# BMS_Rev2_SSR.net
KiCad netlist of a schematic drawn in EAGLE
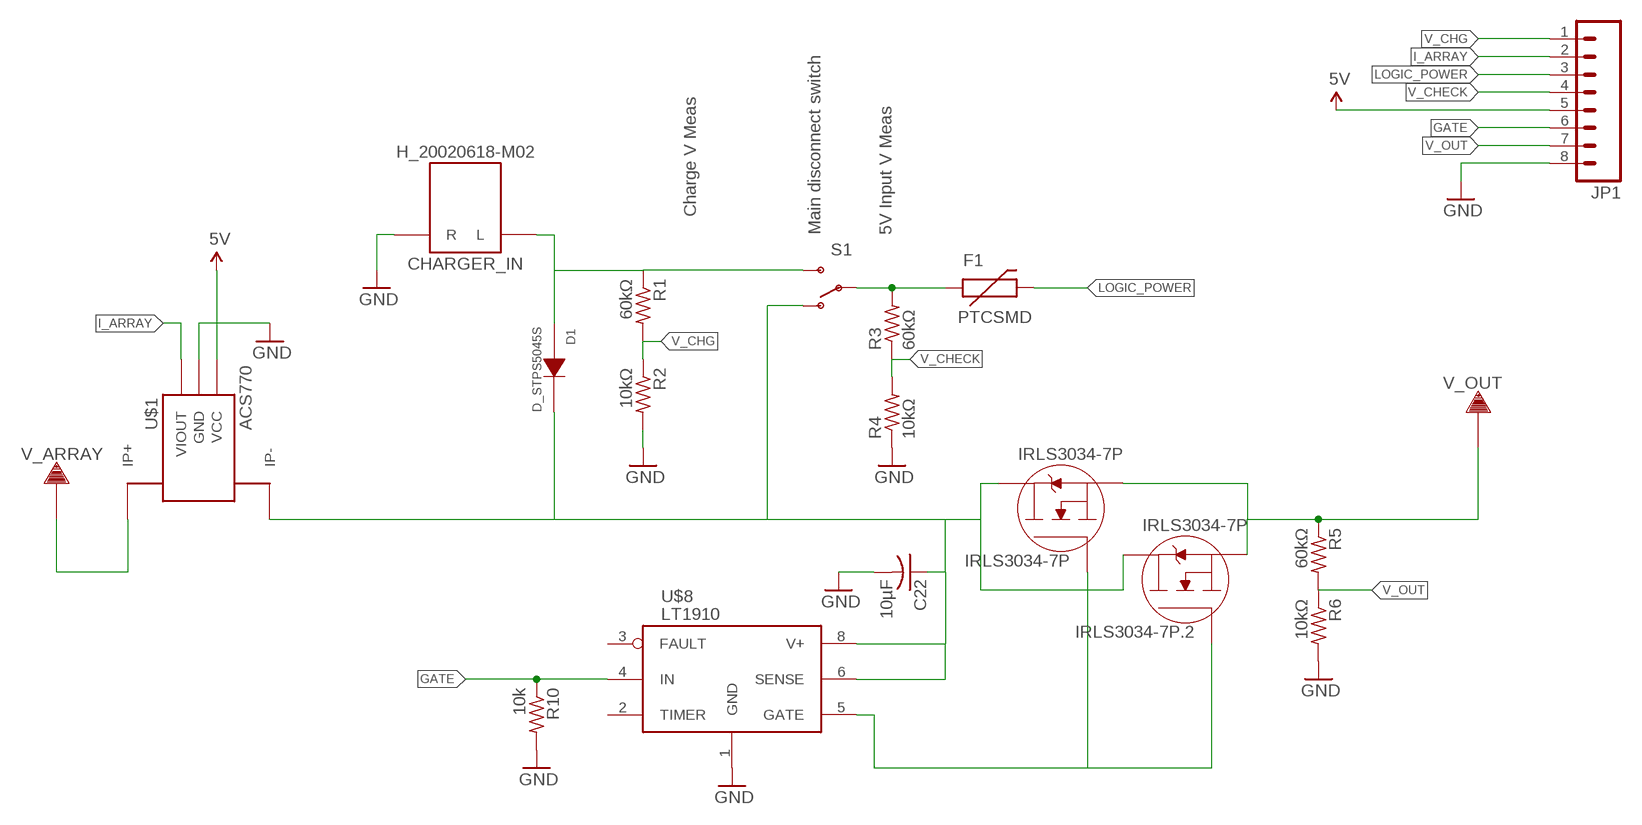
[diagram p0: schematic, sheet 1]

(export (version "E")
  (design (tool "Eeschema 10.0.6"))
  (components
    (comp (ref "C22")
      (value "10µF")
      (footprint "eagle-import:C1206")
      (libsource (lib "eagle-import") (part "C-USC1206"))
    )
    (comp (ref "CHARGER_IN")
      (value "H_20020618-M02")
      (footprint "eagle-import:20020618-M02")
      (libsource (lib "eagle-import") (part "H_20020618-M02"))
    )
    (comp (ref "D1")
      (value "D_STPS5045S")
      (footprint "eagle-import:D2PACK")
      (libsource (lib "eagle-import") (part "D_STPS5045S"))
    )
    (comp (ref "F1")
      (value "PTCSMD")
      (footprint "eagle-import:PTC-1206")
      (libsource (lib "eagle-import") (part "PTCSMD"))
    )
    (comp (ref "IRLS3034-7P")
      (value "IRLS3034-7P")
      (footprint "eagle-import:D2PAK-7")
      (libsource (lib "eagle-import") (part "IRLS3034-7P"))
    )
    (comp (ref "IRLS3034-7P.2")
      (value "IRLS3034-7P")
      (footprint "eagle-import:D2PAK-7")
      (libsource (lib "eagle-import") (part "IRLS3034-7P"))
    )
    (comp (ref "JP1")
      (value "M08BM08B-SRSS-TB")
      (footprint "eagle-import:BM08B-SRSS-TB")
      (libsource (lib "eagle-import") (part "M08BM08B-SRSS-TB"))
    )
    (comp (ref "R1")
      (value "60kΩ")
      (footprint "eagle-import:R1206")
      (libsource (lib "eagle-import") (part "R-US_R1206"))
    )
    (comp (ref "R2")
      (value "10kΩ")
      (footprint "eagle-import:R1206")
      (libsource (lib "eagle-import") (part "R-US_R1206"))
    )
    (comp (ref "R3")
      (value "60kΩ")
      (footprint "eagle-import:R1206")
      (libsource (lib "eagle-import") (part "R-US_R1206"))
    )
    (comp (ref "R4")
      (value "10kΩ")
      (footprint "eagle-import:R1206")
      (libsource (lib "eagle-import") (part "R-US_R1206"))
    )
    (comp (ref "R5")
      (value "60kΩ")
      (footprint "eagle-import:R1206")
      (libsource (lib "eagle-import") (part "R-US_R1206"))
    )
    (comp (ref "R6")
      (value "10kΩ")
      (footprint "eagle-import:R1206")
      (libsource (lib "eagle-import") (part "R-US_R1206"))
    )
    (comp (ref "R10")
      (value "10k")
      (footprint "eagle-import:R1206")
      (libsource (lib "eagle-import") (part "R-US_R1206"))
    )
    (comp (ref "S1")
      (value "SWITCH-SPDTPTH")
      (footprint "eagle-import:SWITCH-SPDT")
      (libsource (lib "eagle-import") (part "SWITCH-SPDTPTH"))
    )
    (comp (ref "U$1")
      (value "ACS770")
      (footprint "eagle-import:PFF_LEADFORM")
      (libsource (lib "eagle-import") (part "ACS770"))
    )
    (comp (ref "U$8")
      (value "LT1910")
      (footprint "eagle-import:SO8")
      (libsource (lib "eagle-import") (part "LT1910"))
    )
    (comp (ref "V_ARRAY")
      (value "TERMINAL_HOLE")
      (footprint "eagle-import:LARGE_TERMINAL_HOLE")
      (libsource (lib "eagle-import") (part "TERMINAL_HOLE"))
    )
    (comp (ref "V_OUT")
      (value "TERMINAL_HOLE")
      (footprint "eagle-import:LARGE_TERMINAL_HOLE")
      (libsource (lib "eagle-import") (part "TERMINAL_HOLE"))
    )
  )
  (nets
    (net (code "1") (name "5V") (class "Default")
      (node (ref "JP1") (pin "5") (pinfunction "5_5") (pintype "passive"))
      (node (ref "U$1") (pin "1") (pinfunction "VCC_1") (pintype "bidirectional"))
    )
    (net (code "2") (name "GATE") (class "Default")
      (node (ref "JP1") (pin "6") (pinfunction "6_6") (pintype "passive"))
      (node (ref "R10") (pin "1") (pinfunction "1_1") (pintype "passive"))
      (node (ref "U$8") (pin "4") (pinfunction "IN_4") (pintype "bidirectional"))
    )
    (net (code "3") (name "GND") (class "Default")
      (node (ref "C22") (pin "2") (pinfunction "2_2") (pintype "passive"))
      (node (ref "CHARGER_IN") (pin "R1") (pinfunction "R_R1") (pintype "bidirectional"))
      (node (ref "CHARGER_IN") (pin "R2") (pinfunction "R_R2") (pintype "bidirectional"))
      (node (ref "JP1") (pin "8") (pinfunction "8_8") (pintype "passive"))
      (node (ref "R10") (pin "2") (pinfunction "2_2") (pintype "passive"))
      (node (ref "R2") (pin "2") (pinfunction "2_2") (pintype "passive"))
      (node (ref "R4") (pin "1") (pinfunction "1_1") (pintype "passive"))
      (node (ref "R6") (pin "2") (pinfunction "2_2") (pintype "passive"))
      (node (ref "U$1") (pin "2") (pinfunction "GND_2") (pintype "bidirectional"))
      (node (ref "U$8") (pin "1") (pinfunction "GND_1") (pintype "bidirectional"))
    )
    (net (code "4") (name "I_ARRAY") (class "Default")
      (node (ref "JP1") (pin "2") (pinfunction "2_2") (pintype "passive"))
      (node (ref "U$1") (pin "3") (pinfunction "VIOUT_3") (pintype "bidirectional"))
    )
    (net (code "5") (name "LOGIC_POWER") (class "Default")
      (node (ref "F1") (pin "2") (pinfunction "2_2") (pintype "bidirectional"))
      (node (ref "JP1") (pin "3") (pinfunction "3_3") (pintype "passive"))
    )
    (net (code "6") (name "Net-(D1-K)") (class "Default")
      (node (ref "C22") (pin "1") (pinfunction "1_1") (pintype "passive"))
      (node (ref "D1") (pin "TAB") (pinfunction "K_TAB") (pintype "bidirectional"))
      (node (ref "IRLS3034-7P") (pin "PAD") (pinfunction "DRAIN_PAD") (pintype "bidirectional"))
      (node (ref "IRLS3034-7P.2") (pin "PAD") (pinfunction "DRAIN_PAD") (pintype "bidirectional"))
      (node (ref "S1") (pin "1") (pinfunction "O_1") (pintype "passive"))
      (node (ref "U$1") (pin "5_1") (pinfunction "IP-_5_1") (pintype "bidirectional"))
      (node (ref "U$1") (pin "5_10") (pinfunction "IP-_5_10") (pintype "bidirectional"))
      (node (ref "U$1") (pin "5_11") (pinfunction "IP-_5_11") (pintype "bidirectional"))
      (node (ref "U$1") (pin "5_12") (pinfunction "IP-_5_12") (pintype "bidirectional"))
      (node (ref "U$1") (pin "5_13") (pinfunction "IP-_5_13") (pintype "bidirectional"))
      (node (ref "U$1") (pin "5_14") (pinfunction "IP-_5_14") (pintype "bidirectional"))
      (node (ref "U$1") (pin "5_15") (pinfunction "IP-_5_15") (pintype "bidirectional"))
      (node (ref "U$1") (pin "5_16") (pinfunction "IP-_5_16") (pintype "bidirectional"))
      (node (ref "U$1") (pin "5_2") (pinfunction "IP-_5_2") (pintype "bidirectional"))
      (node (ref "U$1") (pin "5_3") (pinfunction "IP-_5_3") (pintype "bidirectional"))
      (node (ref "U$1") (pin "5_4") (pinfunction "IP-_5_4") (pintype "bidirectional"))
      (node (ref "U$1") (pin "5_5") (pinfunction "IP-_5_5") (pintype "bidirectional"))
      (node (ref "U$1") (pin "5_6") (pinfunction "IP-_5_6") (pintype "bidirectional"))
      (node (ref "U$1") (pin "5_7") (pinfunction "IP-_5_7") (pintype "bidirectional"))
      (node (ref "U$1") (pin "5_8") (pinfunction "IP-_5_8") (pintype "bidirectional"))
      (node (ref "U$1") (pin "5_9") (pinfunction "IP-_5_9") (pintype "bidirectional"))
      (node (ref "U$1") (pin "5_B") (pinfunction "IP-_5_B") (pintype "bidirectional"))
      (node (ref "U$1") (pin "5_T") (pinfunction "IP-_5_T") (pintype "bidirectional"))
      (node (ref "U$8") (pin "6") (pinfunction "SENSE_6") (pintype "bidirectional"))
      (node (ref "U$8") (pin "8") (pinfunction "V+_8") (pintype "bidirectional"))
    )
    (net (code "7") (name "Net-(IRLS3034-7P-GATE)") (class "Default")
      (node (ref "IRLS3034-7P") (pin "1") (pinfunction "GATE_1") (pintype "bidirectional"))
      (node (ref "IRLS3034-7P.2") (pin "1") (pinfunction "GATE_1") (pintype "bidirectional"))
      (node (ref "U$8") (pin "5") (pinfunction "GATE_5") (pintype "bidirectional"))
    )
    (net (code "8") (name "Net-(IRLS3034-7P-SOURCE-Pad2)") (class "Default")
      (node (ref "IRLS3034-7P") (pin "2") (pinfunction "SOURCE_2") (pintype "bidirectional"))
      (node (ref "IRLS3034-7P") (pin "3") (pinfunction "SOURCE_3") (pintype "bidirectional"))
      (node (ref "IRLS3034-7P") (pin "4") (pinfunction "SOURCE_4") (pintype "bidirectional"))
      (node (ref "IRLS3034-7P") (pin "5") (pinfunction "SOURCE_5") (pintype "bidirectional"))
      (node (ref "IRLS3034-7P") (pin "6") (pinfunction "SOURCE_6") (pintype "bidirectional"))
      (node (ref "IRLS3034-7P.2") (pin "2") (pinfunction "SOURCE_2") (pintype "bidirectional"))
      (node (ref "IRLS3034-7P.2") (pin "3") (pinfunction "SOURCE_3") (pintype "bidirectional"))
      (node (ref "IRLS3034-7P.2") (pin "4") (pinfunction "SOURCE_4") (pintype "bidirectional"))
      (node (ref "IRLS3034-7P.2") (pin "5") (pinfunction "SOURCE_5") (pintype "bidirectional"))
      (node (ref "IRLS3034-7P.2") (pin "6") (pinfunction "SOURCE_6") (pintype "bidirectional"))
      (node (ref "R5") (pin "1") (pinfunction "1_1") (pintype "passive"))
      (node (ref "V_OUT") (pin "P$1") (pinfunction "P$1_P$1") (pintype "bidirectional"))
    )
    (net (code "9") (name "Net-(S1-P)") (class "Default")
      (node (ref "F1") (pin "1") (pinfunction "1_1") (pintype "bidirectional"))
      (node (ref "R3") (pin "2") (pinfunction "2_2") (pintype "passive"))
      (node (ref "S1") (pin "2") (pinfunction "P_2") (pintype "passive"))
    )
    (net (code "10") (name "Net-(S1-S)") (class "Default")
      (node (ref "CHARGER_IN") (pin "L1") (pinfunction "L_L1") (pintype "bidirectional"))
      (node (ref "CHARGER_IN") (pin "L2") (pinfunction "L_L2") (pintype "bidirectional"))
      (node (ref "D1") (pin "1") (pinfunction "A_1") (pintype "bidirectional"))
      (node (ref "D1") (pin "2") (pinfunction "A_2") (pintype "bidirectional"))
      (node (ref "R1") (pin "1") (pinfunction "1_1") (pintype "passive"))
      (node (ref "S1") (pin "3") (pinfunction "S_3") (pintype "passive"))
    )
    (net (code "11") (name "Net-(U$1-IP+-Pad4_1)") (class "Default")
      (node (ref "U$1") (pin "4_1") (pinfunction "IP+_4_1") (pintype "bidirectional"))
      (node (ref "U$1") (pin "4_10") (pinfunction "IP+_4_10") (pintype "bidirectional"))
      (node (ref "U$1") (pin "4_11") (pinfunction "IP+_4_11") (pintype "bidirectional"))
      (node (ref "U$1") (pin "4_12") (pinfunction "IP+_4_12") (pintype "bidirectional"))
      (node (ref "U$1") (pin "4_13") (pinfunction "IP+_4_13") (pintype "bidirectional"))
      (node (ref "U$1") (pin "4_14") (pinfunction "IP+_4_14") (pintype "bidirectional"))
      (node (ref "U$1") (pin "4_15") (pinfunction "IP+_4_15") (pintype "bidirectional"))
      (node (ref "U$1") (pin "4_16") (pinfunction "IP+_4_16") (pintype "bidirectional"))
      (node (ref "U$1") (pin "4_2") (pinfunction "IP+_4_2") (pintype "bidirectional"))
      (node (ref "U$1") (pin "4_3") (pinfunction "IP+_4_3") (pintype "bidirectional"))
      (node (ref "U$1") (pin "4_4") (pinfunction "IP+_4_4") (pintype "bidirectional"))
      (node (ref "U$1") (pin "4_5") (pinfunction "IP+_4_5") (pintype "bidirectional"))
      (node (ref "U$1") (pin "4_6") (pinfunction "IP+_4_6") (pintype "bidirectional"))
      (node (ref "U$1") (pin "4_7") (pinfunction "IP+_4_7") (pintype "bidirectional"))
      (node (ref "U$1") (pin "4_8") (pinfunction "IP+_4_8") (pintype "bidirectional"))
      (node (ref "U$1") (pin "4_9") (pinfunction "IP+_4_9") (pintype "bidirectional"))
      (node (ref "U$1") (pin "4_B") (pinfunction "IP+_4_B") (pintype "bidirectional"))
      (node (ref "U$1") (pin "4_T") (pinfunction "IP+_4_T") (pintype "bidirectional"))
      (node (ref "V_ARRAY") (pin "P$1") (pinfunction "P$1_P$1") (pintype "bidirectional"))
    )
    (net (code "12") (name "V_CHECK") (class "Default")
      (node (ref "JP1") (pin "4") (pinfunction "4_4") (pintype "passive"))
      (node (ref "R3") (pin "1") (pinfunction "1_1") (pintype "passive"))
      (node (ref "R4") (pin "2") (pinfunction "2_2") (pintype "passive"))
    )
    (net (code "13") (name "V_CHG") (class "Default")
      (node (ref "JP1") (pin "1") (pinfunction "1_1") (pintype "passive"))
      (node (ref "R1") (pin "2") (pinfunction "2_2") (pintype "passive"))
      (node (ref "R2") (pin "1") (pinfunction "1_1") (pintype "passive"))
    )
    (net (code "14") (name "V_OUT") (class "Default")
      (node (ref "JP1") (pin "7") (pinfunction "7_7") (pintype "passive"))
      (node (ref "R5") (pin "2") (pinfunction "2_2") (pintype "passive"))
      (node (ref "R6") (pin "1") (pinfunction "1_1") (pintype "passive"))
    )
    (net (code "15") (name "unconnected-(U$8-FAULT-Pad3)") (class "Default")
      (node (ref "U$8") (pin "3") (pinfunction "FAULT_3") (pintype "bidirectional"))
    )
    (net (code "16") (name "unconnected-(U$8-TIMER-Pad2)") (class "Default")
      (node (ref "U$8") (pin "2") (pinfunction "TIMER_2") (pintype "bidirectional"))
    )
  )
)
